# INTERFACE.net
KiCad netlist of a schematic drawn in Altium Designer
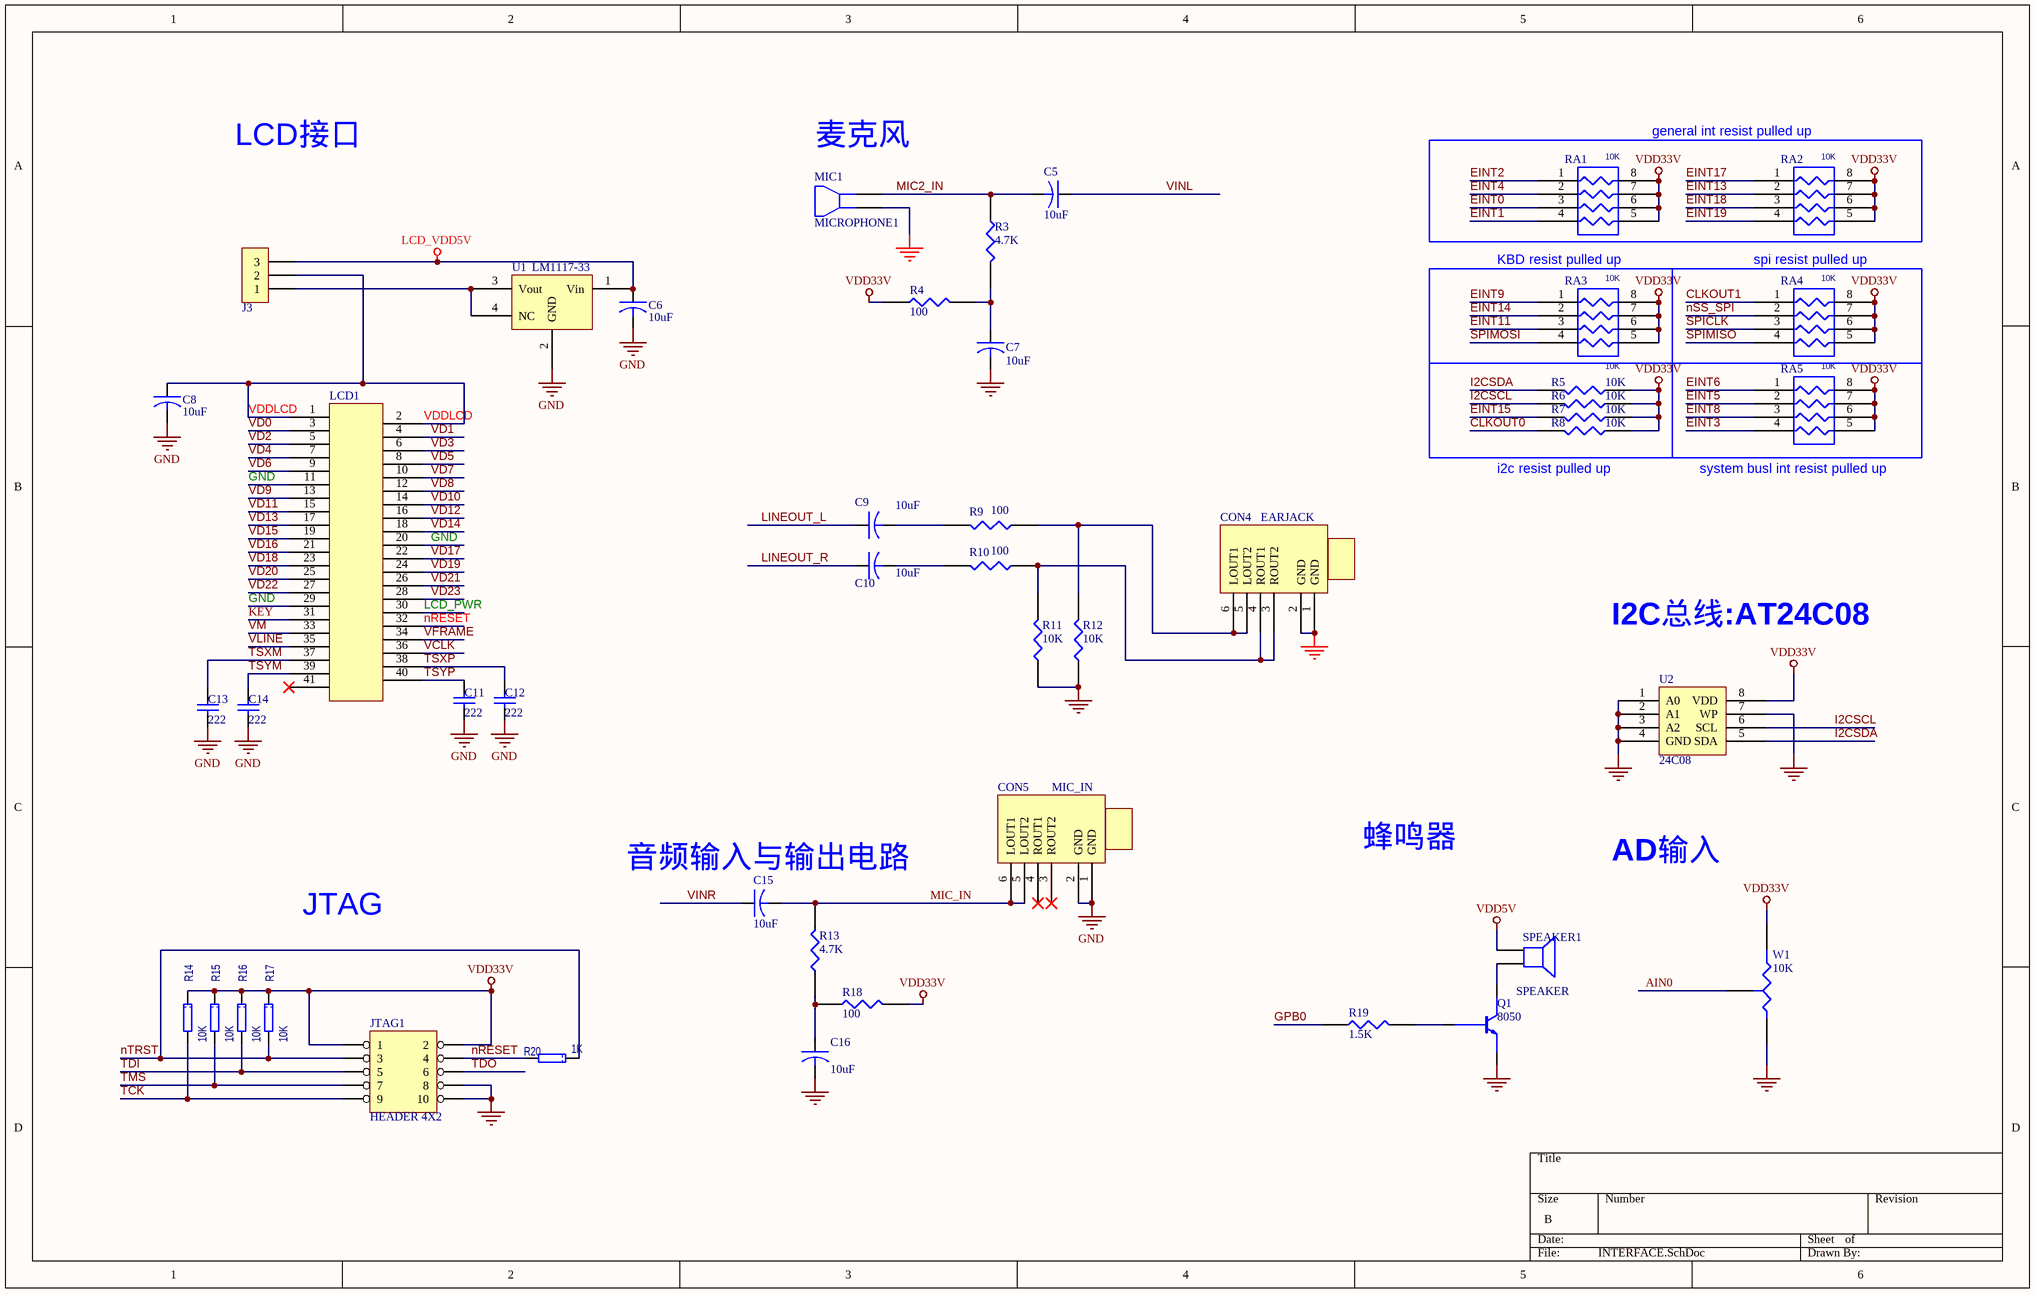
[diagram p0: INTERFACE.SchDoc]

(export (version "E")
  (design (tool "Eeschema 10.0.6"))
  (components
    (comp (ref "C5")
      (value "10uF")
      (footprint "0805C")
      (description "Capacitor")
      (libsource (lib "") (part "CAPACITOR_1"))
    )
    (comp (ref "C6")
      (value "10uF")
      (footprint "3216A")
      (description "Capacitor")
      (libsource (lib "*") (part "CAPACITOR"))
    )
    (comp (ref "C7")
      (value "10uF")
      (footprint "0805C")
      (description "Capacitor")
      (libsource (lib "") (part "CAPACITOR_1"))
    )
    (comp (ref "C8")
      (value "10uF")
      (footprint "3216A")
      (description "Capacitor")
      (libsource (lib "*") (part "CAPACITOR"))
    )
    (comp (ref "C9")
      (value "10uF")
      (footprint "0805C")
      (description "Capacitor")
      (libsource (lib "*") (part "CAPACITOR"))
    )
    (comp (ref "C10")
      (value "10uF")
      (footprint "0805C")
      (description "Capacitor")
      (libsource (lib "*") (part "CAPACITOR"))
    )
    (comp (ref "C11")
      (value "222")
      (footprint "0603A")
      (description "Capacitor")
      (fields (field (name "PUBLISHER") "Altium Limited"))
      (libsource (lib "Miscellaneous Devices") (part "Cap"))
    )
    (comp (ref "C12")
      (value "222")
      (footprint "0603A")
      (description "Capacitor")
      (fields (field (name "PUBLISHER") "Altium Limited"))
      (libsource (lib "Miscellaneous Devices") (part "Cap"))
    )
    (comp (ref "C13")
      (value "222")
      (footprint "0603A")
      (description "Capacitor")
      (fields (field (name "PUBLISHER") "Altium Limited"))
      (libsource (lib "Miscellaneous Devices") (part "Cap"))
    )
    (comp (ref "C14")
      (value "222")
      (footprint "0603A")
      (description "Capacitor")
      (fields (field (name "PUBLISHER") "Altium Limited"))
      (libsource (lib "Miscellaneous Devices") (part "Cap"))
    )
    (comp (ref "C15")
      (value "10uF")
      (footprint "0805C")
      (description "Capacitor")
      (libsource (lib "*") (part "CAPACITOR"))
    )
    (comp (ref "C16")
      (value "10uF")
      (footprint "0805C")
      (description "Capacitor")
      (libsource (lib "*") (part "CAPACITOR"))
    )
    (comp (ref "CON4") (value "EARJACK") (footprint "MIN_PHONE") (libsource (lib "Schlib1") (part "EARJACK")))
    (comp (ref "CON5") (value "MIC_IN") (footprint "MIN_PHONE") (libsource (lib "Schlib1") (part "EARJACK")))
    (comp (ref "J3")
      (value "J3")
      (footprint "SIP3S")
      (description "Connector")
      (libsource (lib "*") (part "CON3"))
    )
    (comp (ref "JTAG1") (value "HEADER 4X2") (footprint "IDC10S") (libsource (lib "*") (part "HEADER 5X2")))
    (comp (ref "LCD1") (value "LCD41P") (footprint "LCD-40") (libsource (lib "*") (part "LCD41P")))
    (comp (ref "MIC1")
      (value "MICROPHONE1")
      (footprint "MIC2")
      (description "Microphone")
      (libsource (lib "*") (part "MICROPHONE1"))
    )
    (comp (ref "Q1") (value "8050") (footprint "SOT23") (libsource (lib "*") (part "NPN")))
    (comp (ref "R3") (value "4.7K") (footprint "0603R") (libsource (lib "*") (part "RES1")))
    (comp (ref "R4") (value "100") (footprint "0603R") (libsource (lib "*") (part "RES1")))
    (comp (ref "R5") (value "10K") (footprint "0603R") (libsource (lib "*") (part "RES1")))
    (comp (ref "R6") (value "10K") (footprint "0603R") (libsource (lib "*") (part "RES1")))
    (comp (ref "R7") (value "10K") (footprint "0603R") (libsource (lib "*") (part "RES1")))
    (comp (ref "R8") (value "10K") (footprint "0603R") (libsource (lib "*") (part "RES1")))
    (comp (ref "R9") (value "100") (footprint "0603R") (libsource (lib "*") (part "RES1")))
    (comp (ref "R10") (value "100") (footprint "0603R") (libsource (lib "*") (part "RES1")))
    (comp (ref "R11") (value "10K") (footprint "0603R") (libsource (lib "*") (part "RES1")))
    (comp (ref "R12") (value "10K") (footprint "0603R") (libsource (lib "*") (part "RES1")))
    (comp (ref "R13") (value "4.7K") (footprint "0603R") (libsource (lib "*") (part "RES1")))
    (comp (ref "R14") (value "10K") (footprint "0603R") (libsource (lib "*") (part "RES")))
    (comp (ref "R15") (value "10K") (footprint "0603R") (libsource (lib "*") (part "RES")))
    (comp (ref "R16") (value "10K") (footprint "0603R") (libsource (lib "*") (part "RES")))
    (comp (ref "R17") (value "10K") (footprint "0603R") (libsource (lib "*") (part "RES")))
    (comp (ref "R18") (value "100") (footprint "0603R") (libsource (lib "*") (part "RES1")))
    (comp (ref "R19") (value "1.5K") (footprint "0603R") (libsource (lib "*") (part "RES1")))
    (comp (ref "R20") (value "1K") (footprint "0603R") (libsource (lib "*") (part "RES")))
    (comp (ref "RA1") (value "10K") (footprint "R-AR4") (libsource (lib "*") (part "RP4R")))
    (comp (ref "RA2") (value "10K") (footprint "R-AR4") (libsource (lib "*") (part "RP4R")))
    (comp (ref "RA3") (value "10K") (footprint "R-AR4") (libsource (lib "*") (part "RP4R")))
    (comp (ref "RA4") (value "10K") (footprint "R-AR4") (libsource (lib "*") (part "RP4R")))
    (comp (ref "RA5") (value "10K") (footprint "R-AR4") (libsource (lib "*") (part "RP4R")))
    (comp (ref "SPEAKER1") (value "SPEAKER") (footprint "SPEAKER-9") (libsource (lib "*") (part "SPEAKER")))
    (comp (ref "U1") (value "LM1117-33") (footprint "TO-252") (libsource (lib "*") (part "LM1117-33")))
    (comp (ref "U2")
      (value "24C08")
      (footprint "SOP8-50-160")
      (description "U")
      (libsource (lib "*") (part "AT24LC04"))
    )
    (comp (ref "W1") (value "10K") (footprint "R_ADJ7") (libsource (lib "*") (part "RESISTOR TAPPED")))
  )
  (nets
    (net (code "1") (name "/AIN0") (class "Default")
      (node (ref "W1") (pin "3") (pinfunction "TAP_3") (pintype "passive"))
    )
    (net (code "2") (name "/CLKOUT0") (class "Default")
      (node (ref "R8") (pin "2") (pinfunction "2_2") (pintype "passive"))
    )
    (net (code "3") (name "/CLKOUT1") (class "Default")
      (node (ref "RA4") (pin "1") (pinfunction "R1_1") (pintype "passive"))
    )
    (net (code "4") (name "/EINT0") (class "Default")
      (node (ref "RA1") (pin "3") (pinfunction "R3_3") (pintype "passive"))
    )
    (net (code "5") (name "/EINT1") (class "Default")
      (node (ref "RA1") (pin "4") (pinfunction "R4_4") (pintype "passive"))
    )
    (net (code "6") (name "/EINT2") (class "Default")
      (node (ref "RA1") (pin "1") (pinfunction "R1_1") (pintype "passive"))
    )
    (net (code "7") (name "/EINT3") (class "Default")
      (node (ref "RA5") (pin "4") (pinfunction "R4_4") (pintype "passive"))
    )
    (net (code "8") (name "/EINT4") (class "Default")
      (node (ref "RA1") (pin "2") (pinfunction "R2_2") (pintype "passive"))
    )
    (net (code "9") (name "/EINT5") (class "Default")
      (node (ref "RA5") (pin "2") (pinfunction "R2_2") (pintype "passive"))
    )
    (net (code "10") (name "/EINT6") (class "Default")
      (node (ref "RA5") (pin "1") (pinfunction "R1_1") (pintype "passive"))
    )
    (net (code "11") (name "/EINT8") (class "Default")
      (node (ref "RA5") (pin "3") (pinfunction "R3_3") (pintype "passive"))
    )
    (net (code "12") (name "/EINT9") (class "Default")
      (node (ref "RA3") (pin "1") (pinfunction "R1_1") (pintype "passive"))
    )
    (net (code "13") (name "/EINT11") (class "Default")
      (node (ref "RA3") (pin "3") (pinfunction "R3_3") (pintype "passive"))
    )
    (net (code "14") (name "/EINT13") (class "Default")
      (node (ref "RA2") (pin "2") (pinfunction "R2_2") (pintype "passive"))
    )
    (net (code "15") (name "/EINT14") (class "Default")
      (node (ref "RA3") (pin "2") (pinfunction "R2_2") (pintype "passive"))
    )
    (net (code "16") (name "/EINT15") (class "Default")
      (node (ref "R7") (pin "2") (pinfunction "2_2") (pintype "passive"))
    )
    (net (code "17") (name "/EINT17") (class "Default")
      (node (ref "RA2") (pin "1") (pinfunction "R1_1") (pintype "passive"))
    )
    (net (code "18") (name "/EINT18") (class "Default")
      (node (ref "RA2") (pin "3") (pinfunction "R3_3") (pintype "passive"))
    )
    (net (code "19") (name "/EINT19") (class "Default")
      (node (ref "RA2") (pin "4") (pinfunction "R4_4") (pintype "passive"))
    )
    (net (code "20") (name "/GPB0") (class "Default")
      (node (ref "R19") (pin "1") (pinfunction "1_1") (pintype "passive"))
    )
    (net (code "21") (name "/I2CSCL") (class "Default")
      (node (ref "R6") (pin "2") (pinfunction "2_2") (pintype "passive"))
      (node (ref "U2") (pin "6") (pinfunction "SCL_6") (pintype "passive"))
    )
    (net (code "22") (name "/I2CSDA") (class "Default")
      (node (ref "R5") (pin "2") (pinfunction "2_2") (pintype "passive"))
      (node (ref "U2") (pin "5") (pinfunction "SDA_5") (pintype "passive"))
    )
    (net (code "23") (name "/KEY") (class "Default") (node (ref "LCD1") (pin "31") (pintype "passive")))
    (net (code "24") (name "/LCD_PWR") (class "Default") (node (ref "LCD1") (pin "30") (pintype "passive")))
    (net (code "25") (name "/LINEOUT_L") (class "Default")
      (node (ref "C9") (pin "1") (pinfunction "1_1") (pintype "passive"))
    )
    (net (code "26") (name "/LINEOUT_R") (class "Default")
      (node (ref "C10") (pin "1") (pinfunction "1_1") (pintype "passive"))
    )
    (net (code "27") (name "/MIC2_IN") (class "Default")
      (node (ref "C5") (pin "2") (pinfunction "2_2") (pintype "passive"))
      (node (ref "MIC1") (pin "1") (pinfunction "1_1") (pintype "passive"))
      (node (ref "R3") (pin "2") (pinfunction "2_2") (pintype "passive"))
    )
    (net (code "28") (name "/MIC_IN") (class "Default")
      (node (ref "C15") (pin "2") (pinfunction "2_2") (pintype "passive"))
      (node (ref "CON5") (pin "5") (pinfunction "LOUT2_5") (pintype "passive"))
      (node (ref "CON5") (pin "6") (pinfunction "LOUT1_6") (pintype "passive"))
      (node (ref "R13") (pin "2") (pinfunction "2_2") (pintype "passive"))
    )
    (net (code "29") (name "/SPICLK") (class "Default")
      (node (ref "RA4") (pin "3") (pinfunction "R3_3") (pintype "passive"))
    )
    (net (code "30") (name "/SPIMISO") (class "Default")
      (node (ref "RA4") (pin "4") (pinfunction "R4_4") (pintype "passive"))
    )
    (net (code "31") (name "/SPIMOSI") (class "Default")
      (node (ref "RA3") (pin "4") (pinfunction "R4_4") (pintype "passive"))
    )
    (net (code "32") (name "/TCK") (class "Default")
      (node (ref "JTAG1") (pin "9") (pinfunction "9_9") (pintype "passive"))
      (node (ref "R14") (pin "2") (pinfunction "2_2") (pintype "passive"))
    )
    (net (code "33") (name "/TDI") (class "Default")
      (node (ref "JTAG1") (pin "5") (pinfunction "5_5") (pintype "passive"))
      (node (ref "R16") (pin "2") (pinfunction "2_2") (pintype "passive"))
    )
    (net (code "34") (name "/TDO") (class "Default")
      (node (ref "JTAG1") (pin "6") (pinfunction "6_6") (pintype "passive"))
    )
    (net (code "35") (name "/TMS") (class "Default")
      (node (ref "JTAG1") (pin "7") (pinfunction "7_7") (pintype "passive"))
      (node (ref "R15") (pin "2") (pinfunction "2_2") (pintype "passive"))
    )
    (net (code "36") (name "/TSXM") (class "Default")
      (node (ref "C13") (pin "2") (pinfunction "2_2") (pintype "passive"))
      (node (ref "LCD1") (pin "37") (pintype "passive"))
    )
    (net (code "37") (name "/TSXP") (class "Default")
      (node (ref "C12") (pin "2") (pinfunction "2_2") (pintype "passive"))
      (node (ref "LCD1") (pin "38") (pintype "passive"))
    )
    (net (code "38") (name "/TSYM") (class "Default")
      (node (ref "C14") (pin "2") (pinfunction "2_2") (pintype "passive"))
      (node (ref "LCD1") (pin "39") (pintype "passive"))
    )
    (net (code "39") (name "/TSYP") (class "Default")
      (node (ref "C11") (pin "2") (pinfunction "2_2") (pintype "passive"))
      (node (ref "LCD1") (pin "40") (pintype "passive"))
    )
    (net (code "40") (name "/VCLK") (class "Default") (node (ref "LCD1") (pin "36") (pintype "passive")))
    (net (code "41") (name "/VD0") (class "Default") (node (ref "LCD1") (pin "3") (pintype "passive")))
    (net (code "42") (name "/VD1") (class "Default") (node (ref "LCD1") (pin "4") (pintype "passive")))
    (net (code "43") (name "/VD2") (class "Default") (node (ref "LCD1") (pin "5") (pintype "passive")))
    (net (code "44") (name "/VD3") (class "Default") (node (ref "LCD1") (pin "6") (pintype "passive")))
    (net (code "45") (name "/VD4") (class "Default") (node (ref "LCD1") (pin "7") (pintype "passive")))
    (net (code "46") (name "/VD5") (class "Default") (node (ref "LCD1") (pin "8") (pintype "passive")))
    (net (code "47") (name "/VD6") (class "Default") (node (ref "LCD1") (pin "9") (pintype "passive")))
    (net (code "48") (name "/VD7") (class "Default") (node (ref "LCD1") (pin "10") (pintype "passive")))
    (net (code "49") (name "/VD8") (class "Default") (node (ref "LCD1") (pin "12") (pintype "passive")))
    (net (code "50") (name "/VD9") (class "Default") (node (ref "LCD1") (pin "13") (pintype "passive")))
    (net (code "51") (name "/VD10") (class "Default") (node (ref "LCD1") (pin "14") (pintype "passive")))
    (net (code "52") (name "/VD11") (class "Default") (node (ref "LCD1") (pin "15") (pintype "passive")))
    (net (code "53") (name "/VD12") (class "Default") (node (ref "LCD1") (pin "16") (pintype "passive")))
    (net (code "54") (name "/VD13") (class "Default") (node (ref "LCD1") (pin "17") (pintype "passive")))
    (net (code "55") (name "/VD14") (class "Default") (node (ref "LCD1") (pin "18") (pintype "passive")))
    (net (code "56") (name "/VD15") (class "Default") (node (ref "LCD1") (pin "19") (pintype "passive")))
    (net (code "57") (name "/VD16") (class "Default") (node (ref "LCD1") (pin "21") (pintype "passive")))
    (net (code "58") (name "/VD17") (class "Default") (node (ref "LCD1") (pin "22") (pintype "passive")))
    (net (code "59") (name "/VD18") (class "Default") (node (ref "LCD1") (pin "23") (pintype "passive")))
    (net (code "60") (name "/VD19") (class "Default") (node (ref "LCD1") (pin "24") (pintype "passive")))
    (net (code "61") (name "/VD20") (class "Default") (node (ref "LCD1") (pin "25") (pintype "passive")))
    (net (code "62") (name "/VD21") (class "Default") (node (ref "LCD1") (pin "26") (pintype "passive")))
    (net (code "63") (name "/VD22") (class "Default") (node (ref "LCD1") (pin "27") (pintype "passive")))
    (net (code "64") (name "/VD23") (class "Default") (node (ref "LCD1") (pin "28") (pintype "passive")))
    (net (code "65") (name "/VDDLCD") (class "Default")
      (node (ref "C8") (pin "1") (pinfunction "1_1") (pintype "passive"))
      (node (ref "J3") (pin "2") (pinfunction "2_2") (pintype "passive"))
      (node (ref "LCD1") (pin "1") (pintype "passive"))
      (node (ref "LCD1") (pin "2") (pintype "passive"))
    )
    (net (code "66") (name "/VFRAME") (class "Default") (node (ref "LCD1") (pin "34") (pintype "passive")))
    (net (code "67") (name "/VINL") (class "Default")
      (node (ref "C5") (pin "1") (pinfunction "1_1") (pintype "passive"))
    )
    (net (code "68") (name "/VINR") (class "Default")
      (node (ref "C15") (pin "1") (pinfunction "1_1") (pintype "passive"))
    )
    (net (code "69") (name "/VLINE") (class "Default") (node (ref "LCD1") (pin "35") (pintype "passive")))
    (net (code "70") (name "/VM") (class "Default") (node (ref "LCD1") (pin "33") (pintype "passive")))
    (net (code "71") (name "/nRESET") (class "Default")
      (node (ref "JTAG1") (pin "4") (pinfunction "4_4") (pintype "passive"))
      (node (ref "LCD1") (pin "32") (pintype "passive"))
      (node (ref "R20") (pin "2") (pinfunction "2_2") (pintype "passive"))
    )
    (net (code "72") (name "/nSS_SPI") (class "Default")
      (node (ref "RA4") (pin "2") (pinfunction "R2_2") (pintype "passive"))
    )
    (net (code "73") (name "/nTRST") (class "Default")
      (node (ref "JTAG1") (pin "3") (pinfunction "3_3") (pintype "passive"))
      (node (ref "R17") (pin "2") (pinfunction "2_2") (pintype "passive"))
      (node (ref "R20") (pin "1") (pinfunction "1_1") (pintype "passive"))
    )
    (net (code "74") (name "GND") (class "Default")
      (node (ref "C11") (pin "1") (pinfunction "1_1") (pintype "passive"))
      (node (ref "C12") (pin "1") (pinfunction "1_1") (pintype "passive"))
      (node (ref "C13") (pin "1") (pinfunction "1_1") (pintype "passive"))
      (node (ref "C14") (pin "1") (pinfunction "1_1") (pintype "passive"))
      (node (ref "C16") (pin "2") (pinfunction "2_2") (pintype "passive"))
      (node (ref "C6") (pin "2") (pinfunction "2_2") (pintype "passive"))
      (node (ref "C7") (pin "2") (pinfunction "2_2") (pintype "passive"))
      (node (ref "C8") (pin "2") (pinfunction "2_2") (pintype "passive"))
      (node (ref "CON4") (pin "1") (pinfunction "GND_1") (pintype "passive"))
      (node (ref "CON4") (pin "2") (pinfunction "GND_2") (pintype "passive"))
      (node (ref "CON5") (pin "1") (pinfunction "GND_1") (pintype "passive"))
      (node (ref "CON5") (pin "2") (pinfunction "GND_2") (pintype "passive"))
      (node (ref "JTAG1") (pin "10") (pinfunction "10_10") (pintype "passive"))
      (node (ref "JTAG1") (pin "8") (pinfunction "8_8") (pintype "passive"))
      (node (ref "LCD1") (pin "11") (pintype "passive"))
      (node (ref "LCD1") (pin "20") (pintype "passive"))
      (node (ref "LCD1") (pin "29") (pintype "passive"))
      (node (ref "MIC1") (pin "2") (pinfunction "2_2") (pintype "passive"))
      (node (ref "Q1") (pin "E") (pintype "passive"))
      (node (ref "R11") (pin "1") (pinfunction "1_1") (pintype "passive"))
      (node (ref "R12") (pin "1") (pinfunction "1_1") (pintype "passive"))
      (node (ref "U1") (pin "2") (pinfunction "GND_2") (pintype "passive"))
      (node (ref "U2") (pin "1") (pinfunction "A0_1") (pintype "passive"))
      (node (ref "U2") (pin "2") (pinfunction "A1_2") (pintype "passive"))
      (node (ref "U2") (pin "3") (pinfunction "A2_3") (pintype "passive"))
      (node (ref "U2") (pin "4") (pinfunction "GND_4") (pintype "passive"))
      (node (ref "U2") (pin "7") (pinfunction "WP_7") (pintype "passive"))
      (node (ref "W1") (pin "1") (pinfunction "A_1") (pintype "passive"))
    )
    (net (code "75") (name "LCD_VDD5V") (class "Default")
      (node (ref "C6") (pin "1") (pinfunction "1_1") (pintype "passive"))
      (node (ref "J3") (pin "3") (pinfunction "3_3") (pintype "passive"))
      (node (ref "U1") (pin "1") (pinfunction "Vin_1") (pintype "passive"))
    )
    (net (code "76") (name "Net-(C7-Pad1)") (class "Default")
      (node (ref "C7") (pin "1") (pinfunction "1_1") (pintype "passive"))
      (node (ref "R3") (pin "1") (pinfunction "1_1") (pintype "passive"))
      (node (ref "R4") (pin "1") (pinfunction "1_1") (pintype "passive"))
    )
    (net (code "77") (name "Net-(C9-Pad2)") (class "Default")
      (node (ref "C9") (pin "2") (pinfunction "2_2") (pintype "passive"))
      (node (ref "R9") (pin "2") (pinfunction "2_2") (pintype "passive"))
    )
    (net (code "78") (name "Net-(C10-Pad2)") (class "Default")
      (node (ref "C10") (pin "2") (pinfunction "2_2") (pintype "passive"))
      (node (ref "R10") (pin "2") (pinfunction "2_2") (pintype "passive"))
    )
    (net (code "79") (name "Net-(C16-Pad1)") (class "Default")
      (node (ref "C16") (pin "1") (pinfunction "1_1") (pintype "passive"))
      (node (ref "R13") (pin "1") (pinfunction "1_1") (pintype "passive"))
      (node (ref "R18") (pin "1") (pinfunction "1_1") (pintype "passive"))
    )
    (net (code "80") (name "Net-(CON4-LOUT1)") (class "Default")
      (node (ref "CON4") (pin "5") (pinfunction "LOUT2_5") (pintype "passive"))
      (node (ref "CON4") (pin "6") (pinfunction "LOUT1_6") (pintype "passive"))
      (node (ref "R12") (pin "2") (pinfunction "2_2") (pintype "passive"))
      (node (ref "R9") (pin "1") (pinfunction "1_1") (pintype "passive"))
    )
    (net (code "81") (name "Net-(CON4-ROUT1)") (class "Default")
      (node (ref "CON4") (pin "3") (pinfunction "ROUT2_3") (pintype "passive"))
      (node (ref "CON4") (pin "4") (pinfunction "ROUT1_4") (pintype "passive"))
      (node (ref "R10") (pin "1") (pinfunction "1_1") (pintype "passive"))
      (node (ref "R11") (pin "2") (pinfunction "2_2") (pintype "passive"))
    )
    (net (code "82") (name "Net-(Q1-PadB)") (class "Default")
      (node (ref "Q1") (pin "B") (pintype "passive"))
      (node (ref "R19") (pin "2") (pinfunction "2_2") (pintype "passive"))
    )
    (net (code "83") (name "Net-(Q1-PadC)") (class "Default")
      (node (ref "Q1") (pin "C") (pintype "passive"))
      (node (ref "SPEAKER1") (pin "2") (pinfunction "2_2") (pintype "passive"))
    )
    (net (code "84") (name "Net-(U1-NC)") (class "Default")
      (node (ref "J3") (pin "1") (pinfunction "1_1") (pintype "passive"))
      (node (ref "U1") (pin "3") (pinfunction "Vout_3") (pintype "passive"))
      (node (ref "U1") (pin "4") (pinfunction "NC_4") (pintype "passive"))
    )
    (net (code "85") (name "VDD5V") (class "Default")
      (node (ref "SPEAKER1") (pin "1") (pinfunction "1_1") (pintype "passive"))
    )
    (net (code "86") (name "VDD33V") (class "Default")
      (node (ref "JTAG1") (pin "1") (pinfunction "1_1") (pintype "passive"))
      (node (ref "JTAG1") (pin "2") (pinfunction "2_2") (pintype "passive"))
      (node (ref "R14") (pin "1") (pinfunction "1_1") (pintype "passive"))
      (node (ref "R15") (pin "1") (pinfunction "1_1") (pintype "passive"))
      (node (ref "R16") (pin "1") (pinfunction "1_1") (pintype "passive"))
      (node (ref "R17") (pin "1") (pinfunction "1_1") (pintype "passive"))
      (node (ref "R18") (pin "2") (pinfunction "2_2") (pintype "passive"))
      (node (ref "R4") (pin "2") (pinfunction "2_2") (pintype "passive"))
      (node (ref "R5") (pin "1") (pinfunction "1_1") (pintype "passive"))
      (node (ref "R6") (pin "1") (pinfunction "1_1") (pintype "passive"))
      (node (ref "R7") (pin "1") (pinfunction "1_1") (pintype "passive"))
      (node (ref "R8") (pin "1") (pinfunction "1_1") (pintype "passive"))
      (node (ref "RA1") (pin "5") (pinfunction "R4_5") (pintype "passive"))
      (node (ref "RA1") (pin "6") (pinfunction "R3_6") (pintype "passive"))
      (node (ref "RA1") (pin "7") (pinfunction "R2_7") (pintype "passive"))
      (node (ref "RA1") (pin "8") (pinfunction "R1_8") (pintype "passive"))
      (node (ref "RA2") (pin "5") (pinfunction "R4_5") (pintype "passive"))
      (node (ref "RA2") (pin "6") (pinfunction "R3_6") (pintype "passive"))
      (node (ref "RA2") (pin "7") (pinfunction "R2_7") (pintype "passive"))
      (node (ref "RA2") (pin "8") (pinfunction "R1_8") (pintype "passive"))
      (node (ref "RA3") (pin "5") (pinfunction "R4_5") (pintype "passive"))
      (node (ref "RA3") (pin "6") (pinfunction "R3_6") (pintype "passive"))
      (node (ref "RA3") (pin "7") (pinfunction "R2_7") (pintype "passive"))
      (node (ref "RA3") (pin "8") (pinfunction "R1_8") (pintype "passive"))
      (node (ref "RA4") (pin "5") (pinfunction "R4_5") (pintype "passive"))
      (node (ref "RA4") (pin "6") (pinfunction "R3_6") (pintype "passive"))
      (node (ref "RA4") (pin "7") (pinfunction "R2_7") (pintype "passive"))
      (node (ref "RA4") (pin "8") (pinfunction "R1_8") (pintype "passive"))
      (node (ref "RA5") (pin "5") (pinfunction "R4_5") (pintype "passive"))
      (node (ref "RA5") (pin "6") (pinfunction "R3_6") (pintype "passive"))
      (node (ref "RA5") (pin "7") (pinfunction "R2_7") (pintype "passive"))
      (node (ref "RA5") (pin "8") (pinfunction "R1_8") (pintype "passive"))
      (node (ref "U2") (pin "8") (pinfunction "VDD_8") (pintype "passive"))
      (node (ref "W1") (pin "2") (pinfunction "B_2") (pintype "passive"))
    )
    (net (code "87") (name "unconnected-(CON5-ROUT1-Pad4)") (class "Default")
      (node (ref "CON5") (pin "4") (pinfunction "ROUT1_4") (pintype "passive+no_connect"))
    )
    (net (code "88") (name "unconnected-(CON5-ROUT2-Pad3)") (class "Default")
      (node (ref "CON5") (pin "3") (pinfunction "ROUT2_3") (pintype "passive+no_connect"))
    )
    (net (code "89") (name "unconnected-(LCD1-Pad41)") (class "Default")
      (node (ref "LCD1") (pin "41") (pintype "passive+no_connect"))
    )
  )
)
